# CAN.net
KiCad netlist of a schematic drawn in Altium Designer
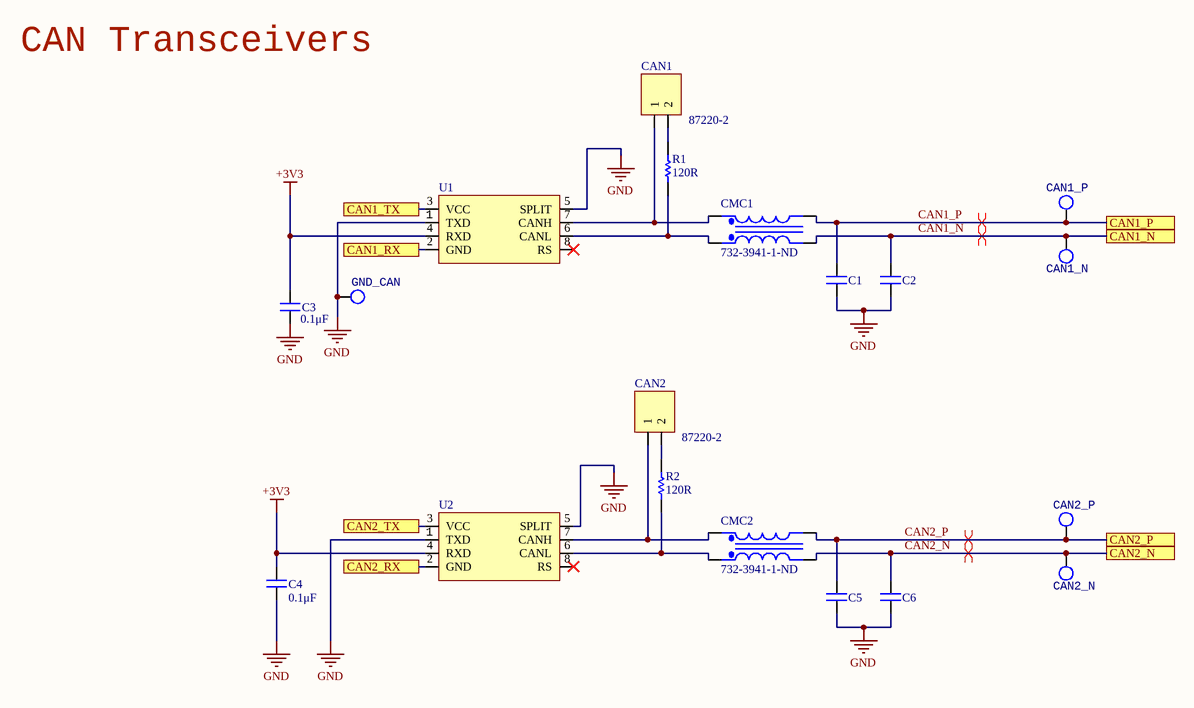
[diagram p0: CAN.SchDoc]

(export (version "E")
  (design (tool "Eeschema 10.0.6"))
  (components
    (comp (ref "C1")
      (value "CAP_33pF_50V_0603")
      (footprint "CAPC0603(1608)55_N")
      (description "CAP CER 33PF 50V C0G/NP0")
      (fields (field (name "VOLTAGE") "50V") (field (name "TOLERANCE") "5%"))
      (libsource (lib "UWRT_Schematic_Library_2020") (part "CAP_33pF_50V_0603"))
    )
    (comp (ref "C2")
      (value "CAP_33pF_50V_0603")
      (footprint "CAPC0603(1608)55_N")
      (description "CAP CER 33PF 50V C0G/NP0")
      (fields (field (name "VOLTAGE") "50V") (field (name "TOLERANCE") "5%"))
      (libsource (lib "UWRT_Schematic_Library_2020") (part "CAP_33pF_50V_0603"))
    )
    (comp (ref "C3")
      (value "0.1μF")
      (footprint "CAPC0603(1608)55_N")
      (description "CAP CER 0.1UF 50V X7R 0603")
      (fields (field (name "Comment") "CAP_0.1uF_50V_0603"))
      (libsource (lib "UWRT_Schematic_Library_2020") (part "CAP_0.1uF_50V_0603"))
    )
    (comp (ref "C4")
      (value "0.1μF")
      (footprint "CAPC0603(1608)55_N")
      (description "CAP CER 0.1UF 50V X7R 0603")
      (fields (field (name "Comment") "CAP_0.1uF_50V_0603"))
      (libsource (lib "UWRT_Schematic_Library_2020") (part "CAP_0.1uF_50V_0603"))
    )
    (comp (ref "C5")
      (value "CAP_33pF_50V_0603")
      (footprint "CAPC0603(1608)55_N")
      (description "CAP CER 33PF 50V C0G/NP0")
      (fields (field (name "VOLTAGE") "50V") (field (name "TOLERANCE") "5%"))
      (libsource (lib "UWRT_Schematic_Library_2020") (part "CAP_33pF_50V_0603"))
    )
    (comp (ref "C6")
      (value "CAP_33pF_50V_0603")
      (footprint "CAPC0603(1608)55_N")
      (description "CAP CER 33PF 50V C0G/NP0")
      (fields (field (name "VOLTAGE") "50V") (field (name "TOLERANCE") "5%"))
      (libsource (lib "UWRT_Schematic_Library_2020") (part "CAP_33pF_50V_0603"))
    )
    (comp (ref "CAN1")
      (value "JUMPER_2")
      (footprint "HDR1X2")
      (description "HEADER 2X1")
      (fields (field (name "MANUFACTURER PART NUMBER 1") "87220-2"))
      (libsource (lib "UWRT_Schematic_Library_2020") (part "JUMPER_2"))
    )
    (comp (ref "CAN1_N")
      (value "TESTPOINT_LOOP")
      (footprint "TESTPOINT_LOOP")
      (description "Loop testpoint through-hole pad")
      (libsource (lib "UWRT_Schematic_Library_2020") (part "TESTPOINT_LOOP"))
    )
    (comp (ref "CAN1_P")
      (value "TESTPOINT_LOOP")
      (footprint "TESTPOINT_LOOP")
      (description "Loop testpoint through-hole pad")
      (libsource (lib "UWRT_Schematic_Library_2020") (part "TESTPOINT_LOOP"))
    )
    (comp (ref "CAN2")
      (value "JUMPER_2")
      (footprint "HDR1X2")
      (description "HEADER 2X1")
      (fields (field (name "MANUFACTURER PART NUMBER 1") "87220-2"))
      (libsource (lib "UWRT_Schematic_Library_2020") (part "JUMPER_2"))
    )
    (comp (ref "CAN2_N")
      (value "TESTPOINT_LOOP")
      (footprint "TESTPOINT_LOOP")
      (description "Loop testpoint through-hole pad")
      (libsource (lib "UWRT_Schematic_Library_2020") (part "TESTPOINT_LOOP"))
    )
    (comp (ref "CAN2_P")
      (value "TESTPOINT_LOOP")
      (footprint "TESTPOINT_LOOP")
      (description "Loop testpoint through-hole pad")
      (libsource (lib "UWRT_Schematic_Library_2020") (part "TESTPOINT_LOOP"))
    )
    (comp (ref "CMC1")
      (value "CMC_51uH")
      (footprint "744212510")
      (description "CMC 51uH 300MA 2LN SMD")
      (fields (field (name "TOLERANCE") "50%") (field (name "SUPPLIER PART NUMBER 1") "732-3941-1-ND"))
      (libsource (lib "UWRT_Schematic_Library_2020") (part "CMC_51uH"))
    )
    (comp (ref "CMC2")
      (value "CMC_51uH")
      (footprint "744212510")
      (description "CMC 51uH 300MA 2LN SMD")
      (fields (field (name "TOLERANCE") "50%") (field (name "SUPPLIER PART NUMBER 1") "732-3941-1-ND"))
      (libsource (lib "UWRT_Schematic_Library_2020") (part "CMC_51uH"))
    )
    (comp (ref "GND_CAN")
      (value "TESTPOINT_LOOP")
      (footprint "TESTPOINT_LOOP")
      (description "Loop testpoint through-hole pad")
      (libsource (lib "UWRT_Schematic_Library_2020") (part "TESTPOINT_LOOP"))
    )
    (comp (ref "R1")
      (value "120R")
      (footprint "RESC0603(1608)_N")
      (description "RES SMD 120 OHM 5% 1/10W 0603")
      (fields (field (name "MANUFACTURER") "Yageo") (field (name "MPN") "RC0603JR-07120RL"))
      (libsource (lib "UWRT_Schematic_Library_2020") (part "RES_120R_0603"))
    )
    (comp (ref "R2")
      (value "120R")
      (footprint "RESC0603(1608)_N")
      (description "RES SMD 120 OHM 5% 1/10W 0603")
      (fields (field (name "MANUFACTURER") "Yageo") (field (name "MPN") "RC0603JR-07120RL"))
      (libsource (lib "UWRT_Schematic_Library_2020") (part "RES_120R_0603"))
    )
    (comp (ref "U1")
      (value "IC TXRX CAN")
      (footprint "LT-S8_N")
      (description "IC TXRX CAN 4MBPS 8SO")
      (libsource (lib "UWRT_Schematic_Library_2020") (part "LTC2875"))
    )
    (comp (ref "U2")
      (value "IC TXRX CAN")
      (footprint "LT-S8_N")
      (description "IC TXRX CAN 4MBPS 8SO")
      (libsource (lib "UWRT_Schematic_Library_2020") (part "LTC2875"))
    )
  )
  (nets
    (net (code "1") (name "+3V3") (class "Default")
      (node (ref "C3") (pin "2") (pinfunction "2_2") (pintype "passive"))
      (node (ref "C4") (pin "2") (pinfunction "2_2") (pintype "passive"))
      (node (ref "U1") (pin "4") (pinfunction "RXD_4") (pintype "passive"))
      (node (ref "U2") (pin "4") (pinfunction "RXD_4") (pintype "passive"))
    )
    (net (code "2") (name "/CAN1_N") (class "Default")
      (node (ref "C2") (pin "2") (pinfunction "2_2") (pintype "passive"))
      (node (ref "CAN1_N") (pin "1") (pintype "passive"))
      (node (ref "CMC1") (pin "5") (pinfunction "Pri-_5") (pintype "passive"))
    )
    (net (code "3") (name "/CAN1_P") (class "Default")
      (node (ref "C1") (pin "2") (pinfunction "2_2") (pintype "passive"))
      (node (ref "CAN1_P") (pin "1") (pintype "passive"))
      (node (ref "CMC1") (pin "4") (pinfunction "Sec-_4") (pintype "passive"))
    )
    (net (code "4") (name "/CAN1_RX") (class "Default")
      (node (ref "U1") (pin "2") (pinfunction "GND_2") (pintype "passive"))
    )
    (net (code "5") (name "/CAN1_TX") (class "Default")
      (node (ref "U1") (pin "3") (pinfunction "VCC_3") (pintype "passive"))
    )
    (net (code "6") (name "/CAN2_N") (class "Default")
      (node (ref "C6") (pin "2") (pinfunction "2_2") (pintype "passive"))
      (node (ref "CAN2_N") (pin "1") (pintype "passive"))
      (node (ref "CMC2") (pin "5") (pinfunction "Pri-_5") (pintype "passive"))
    )
    (net (code "7") (name "/CAN2_P") (class "Default")
      (node (ref "C5") (pin "2") (pinfunction "2_2") (pintype "passive"))
      (node (ref "CAN2_P") (pin "1") (pintype "passive"))
      (node (ref "CMC2") (pin "4") (pinfunction "Sec-_4") (pintype "passive"))
    )
    (net (code "8") (name "/CAN2_RX") (class "Default")
      (node (ref "U2") (pin "2") (pinfunction "GND_2") (pintype "passive"))
    )
    (net (code "9") (name "/CAN2_TX") (class "Default")
      (node (ref "U2") (pin "3") (pinfunction "VCC_3") (pintype "passive"))
    )
    (net (code "10") (name "GND") (class "Default")
      (node (ref "C1") (pin "1") (pinfunction "1_1") (pintype "passive"))
      (node (ref "C2") (pin "1") (pinfunction "1_1") (pintype "passive"))
      (node (ref "C3") (pin "1") (pinfunction "1_1") (pintype "passive"))
      (node (ref "C4") (pin "1") (pinfunction "1_1") (pintype "passive"))
      (node (ref "C5") (pin "1") (pinfunction "1_1") (pintype "passive"))
      (node (ref "C6") (pin "1") (pinfunction "1_1") (pintype "passive"))
      (node (ref "GND_CAN") (pin "1") (pintype "passive"))
      (node (ref "U1") (pin "1") (pinfunction "TXD_1") (pintype "passive"))
      (node (ref "U1") (pin "5") (pinfunction "SPLIT_5") (pintype "passive"))
      (node (ref "U2") (pin "1") (pinfunction "TXD_1") (pintype "passive"))
      (node (ref "U2") (pin "5") (pinfunction "SPLIT_5") (pintype "passive"))
    )
    (net (code "11") (name "Net-(CAN1-Pad2)") (class "Default")
      (node (ref "CAN1") (pin "2") (pinfunction "2_2") (pintype "passive"))
      (node (ref "R1") (pin "2") (pinfunction "2_2") (pintype "passive"))
    )
    (net (code "12") (name "Net-(CAN2-Pad2)") (class "Default")
      (node (ref "CAN2") (pin "2") (pinfunction "2_2") (pintype "passive"))
      (node (ref "R2") (pin "2") (pinfunction "2_2") (pintype "passive"))
    )
    (net (code "13") (name "Net-(CMC1-Pri+)") (class "Default")
      (node (ref "CMC1") (pin "1") (pinfunction "Pri+_1") (pintype "passive"))
      (node (ref "R1") (pin "1") (pinfunction "1_1") (pintype "passive"))
      (node (ref "U1") (pin "6") (pinfunction "CANL_6") (pintype "passive"))
    )
    (net (code "14") (name "Net-(CMC1-Sec+)") (class "Default")
      (node (ref "CAN1") (pin "1") (pinfunction "1_1") (pintype "passive"))
      (node (ref "CMC1") (pin "3") (pinfunction "Sec+_3") (pintype "passive"))
      (node (ref "U1") (pin "7") (pinfunction "CANH_7") (pintype "passive"))
    )
    (net (code "15") (name "Net-(CMC2-Pri+)") (class "Default")
      (node (ref "CMC2") (pin "1") (pinfunction "Pri+_1") (pintype "passive"))
      (node (ref "R2") (pin "1") (pinfunction "1_1") (pintype "passive"))
      (node (ref "U2") (pin "6") (pinfunction "CANL_6") (pintype "passive"))
    )
    (net (code "16") (name "Net-(CMC2-Sec+)") (class "Default")
      (node (ref "CAN2") (pin "1") (pinfunction "1_1") (pintype "passive"))
      (node (ref "CMC2") (pin "3") (pinfunction "Sec+_3") (pintype "passive"))
      (node (ref "U2") (pin "7") (pinfunction "CANH_7") (pintype "passive"))
    )
    (net (code "17") (name "unconnected-(U1-RS-Pad8)") (class "Default")
      (node (ref "U1") (pin "8") (pinfunction "RS_8") (pintype "passive+no_connect"))
    )
    (net (code "18") (name "unconnected-(U2-RS-Pad8)") (class "Default")
      (node (ref "U2") (pin "8") (pinfunction "RS_8") (pintype "passive+no_connect"))
    )
  )
)
